# PDMC-S05-V00-Multiplexer.net
KiCad netlist of a schematic drawn in Altium Designer
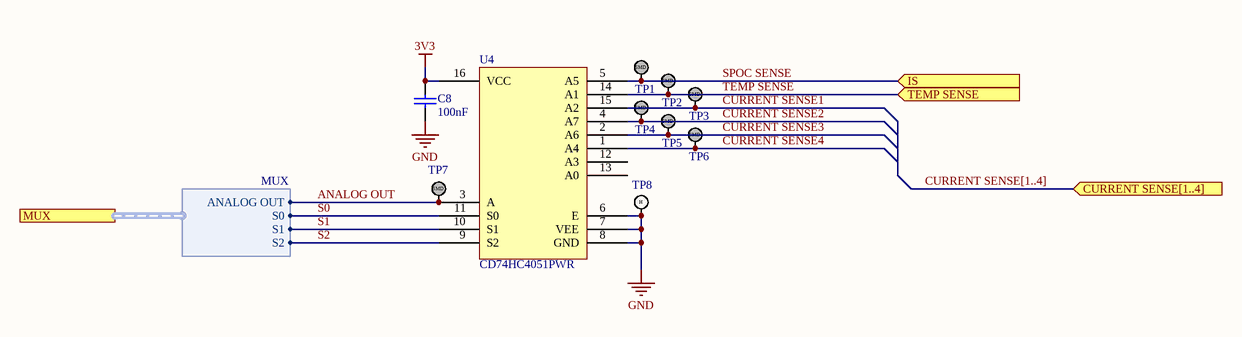
[diagram p0: PDMC-S05-V00-Multiplexer.SchDoc]

(export (version "E")
  (design (tool "Eeschema 10.0.6"))
  (components
    (comp (ref "C8")
      (value "100nF")
      (footprint "Cap_Ceramic_0603")
      (description "Capacitor, Ceramic, SMD, 100nF, 50V, 5%, X7R, 0603")
      (libsource (lib "StandardCapacitors") (part "100nF 50V 5% X7R 0603"))
    )
    (comp (ref "TP1")
      (value "TestPoint_SMD")
      (footprint "TestPointSMD")
      (libsource (lib "StandardTest") (part "TestPoint_SMD"))
    )
    (comp (ref "TP2")
      (value "TestPoint_SMD")
      (footprint "TestPointSMD")
      (libsource (lib "StandardTest") (part "TestPoint_SMD"))
    )
    (comp (ref "TP3")
      (value "TestPoint_SMD")
      (footprint "TestPointSMD")
      (libsource (lib "StandardTest") (part "TestPoint_SMD"))
    )
    (comp (ref "TP4")
      (value "TestPoint_SMD")
      (footprint "TestPointSMD")
      (libsource (lib "StandardTest") (part "TestPoint_SMD"))
    )
    (comp (ref "TP5")
      (value "TestPoint_SMD")
      (footprint "TestPointSMD")
      (libsource (lib "StandardTest") (part "TestPoint_SMD"))
    )
    (comp (ref "TP6")
      (value "TestPoint_SMD")
      (footprint "TestPointSMD")
      (libsource (lib "StandardTest") (part "TestPoint_SMD"))
    )
    (comp (ref "TP7")
      (value "TestPoint_SMD")
      (footprint "TestPointSMD")
      (libsource (lib "StandardTest") (part "TestPoint_SMD"))
    )
    (comp (ref "TP8")
      (value "TestPoint_Hoop_White")
      (footprint "TestPointHoop_WHITE")
      (libsource (lib "StandardTest") (part "TestPoint_Hoop_White"))
    )
    (comp (ref "U4")
      (value "CD74HC4051PWR")
      (footprint "TSSOP-16N")
      (description "IC MUX/DEMUX 8X1 16TSSOP")
      (libsource (lib "PDM-CARD-SCHLib-V00") (part "CD74HC4051PWR"))
    )
  )
  (nets
    (net (code "2") (name "/ANALOG OUT") (class "Default")
      (node (ref "TP7") (pin "1") (pinfunction "1_1") (pintype "passive"))
      (node (ref "U4") (pin "3") (pinfunction "A_3") (pintype "passive"))
    )
    (net (code "3") (name "/CURRENT SENSE1") (class "Default")
      (node (ref "TP3") (pin "1") (pinfunction "1_1") (pintype "passive"))
      (node (ref "U4") (pin "15") (pinfunction "A2_15") (pintype "passive"))
    )
    (net (code "4") (name "/CURRENT SENSE2") (class "Default")
      (node (ref "TP4") (pin "1") (pinfunction "1_1") (pintype "passive"))
      (node (ref "U4") (pin "4") (pinfunction "A7_4") (pintype "passive"))
    )
    (net (code "5") (name "/CURRENT SENSE3") (class "Default")
      (node (ref "TP5") (pin "1") (pinfunction "1_1") (pintype "passive"))
      (node (ref "U4") (pin "2") (pinfunction "A6_2") (pintype "passive"))
    )
    (net (code "6") (name "/CURRENT SENSE4") (class "Default")
      (node (ref "TP6") (pin "1") (pinfunction "1_1") (pintype "passive"))
      (node (ref "U4") (pin "1") (pinfunction "A4_1") (pintype "passive"))
    )
    (net (code "7") (name "/S0") (class "Default")
      (node (ref "U4") (pin "11") (pinfunction "S0_11") (pintype "passive"))
    )
    (net (code "8") (name "/S1") (class "Default")
      (node (ref "U4") (pin "10") (pinfunction "S1_10") (pintype "passive"))
    )
    (net (code "9") (name "/S2") (class "Default")
      (node (ref "U4") (pin "9") (pinfunction "S2_9") (pintype "passive"))
    )
    (net (code "10") (name "/SPOC SENSE") (class "Default")
      (node (ref "TP1") (pin "1") (pinfunction "1_1") (pintype "passive"))
      (node (ref "U4") (pin "5") (pinfunction "A5_5") (pintype "passive"))
    )
    (net (code "11") (name "/TEMP SENSE") (class "Default")
      (node (ref "TP2") (pin "1") (pinfunction "1_1") (pintype "passive"))
      (node (ref "U4") (pin "14") (pinfunction "A1_14") (pintype "passive"))
    )
    (net (code "14") (name "3V3") (class "Default")
      (node (ref "C8") (pin "2") (pinfunction "2_2") (pintype "passive"))
      (node (ref "U4") (pin "16") (pinfunction "VCC_16") (pintype "passive"))
    )
    (net (code "15") (name "GND") (class "Default")
      (node (ref "C8") (pin "1") (pinfunction "1_1") (pintype "passive"))
      (node (ref "TP8") (pin "1") (pinfunction "1_1") (pintype "passive"))
      (node (ref "U4") (pin "6") (pinfunction "E_6") (pintype "passive"))
      (node (ref "U4") (pin "7") (pinfunction "VEE_7") (pintype "passive"))
      (node (ref "U4") (pin "8") (pinfunction "GND_8") (pintype "passive"))
    )
    (net (code "16") (name "unconnected-(U4-A0-Pad13)") (class "Default")
      (node (ref "U4") (pin "13") (pinfunction "A0_13") (pintype "passive"))
    )
    (net (code "17") (name "unconnected-(U4-A3-Pad12)") (class "Default")
      (node (ref "U4") (pin "12") (pinfunction "A3_12") (pintype "passive"))
    )
  )
)
